# POWER.net
KiCad netlist of a schematic drawn in Altium Designer
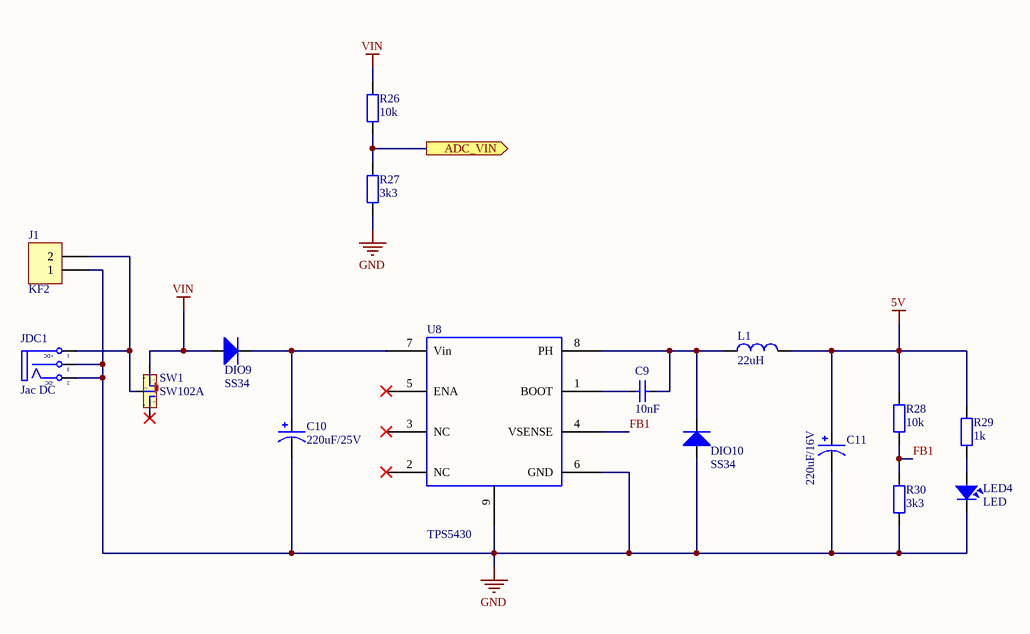
[diagram p0: POWER.SchDoc]

(export (version "E")
  (design (tool "Eeschema 10.0.6"))
  (components
    (comp (ref "C9")
      (value "10nF")
      (footprint "CAP_0805")
      (description "Capacitor")
      (fields (field (name "PUBLISHER") "Altium Limited"))
      (libsource (lib "My Library") (part "CapSMD"))
    )
    (comp (ref "C10")
      (value "220uF/25V")
      (footprint "C8mm")
      (description "Polarized Capacitor (Axial)")
      (fields (field (name "PUBLISHER") "Altium Limited"))
      (libsource (lib "My Library") (part "Cap Pol"))
    )
    (comp (ref "C11")
      (value "220uF/16V")
      (footprint "C8mm")
      (description "Polarized Capacitor (Axial)")
      (fields (field (name "PUBLISHER") "Altium Limited"))
      (libsource (lib "My Library") (part "Cap Pol"))
    )
    (comp (ref "DIO9")
      (value "SS34")
      (footprint "DIO-214AC(SMA)")
      (description "Default Diode")
      (fields (field (name "PUBLISHER") "Altium Limited"))
      (libsource (lib "My Library") (part "Diode SMD"))
    )
    (comp (ref "DIO10")
      (value "SS34")
      (footprint "DIO-214AC(SMA)")
      (description "Default Diode")
      (fields (field (name "PUBLISHER") "Altium Limited"))
      (libsource (lib "My Library") (part "Diode SMD"))
    )
    (comp (ref "J1")
      (value "KF2")
      (footprint "KF2-5.08")
      (fields
        (field (name "MANUFACTURER") "Würth Elektronik eiSos GmbH")
        (field (name "PARTNO") "691103110002")
        (field (name "CREATED BY") "Karrer Zheng")
      )
      (libsource (lib "My Library") (part "KF2"))
    )
    (comp (ref "JDC1")
      (value "Jac DC")
      (footprint "DC-IN")
      (description "Jac DC input")
      (libsource (lib "My Library") (part "DCIN"))
    )
    (comp (ref "L1")
      (value "22uH")
      (footprint "L-SMD-M-7.3x4.5")
      (description "Inductor")
      (libsource (lib "My Library") (part "Inductor"))
    )
    (comp (ref "LED4")
      (value "LED")
      (footprint "LED-0805-Red")
      (description "LED Single colour Green and Red")
      (libsource (lib "My Library") (part "LED"))
    )
    (comp (ref "R26")
      (value "10k")
      (footprint "RES-SMD-0805")
      (description "Resistor SMD")
      (fields
        (field (name "MANUFACTURER") "Generic Components")
        (field (name "PUBLISHER") "Altium Hobart Technology Centre")
      )
      (libsource (lib "My Library") (part "Resistor - SMD"))
    )
    (comp (ref "R27")
      (value "3k3")
      (footprint "RES-SMD-0805")
      (description "Resistor SMD")
      (fields
        (field (name "MANUFACTURER") "Generic Components")
        (field (name "PUBLISHER") "Altium Hobart Technology Centre")
      )
      (libsource (lib "My Library") (part "Resistor - SMD"))
    )
    (comp (ref "R28")
      (value "10k")
      (footprint "RES-SMD-0805")
      (description "Resistor SMD")
      (fields
        (field (name "MANUFACTURER") "Generic Components")
        (field (name "PUBLISHER") "Altium Hobart Technology Centre")
      )
      (libsource (lib "My Library") (part "Resistor - SMD"))
    )
    (comp (ref "R29")
      (value "1k")
      (footprint "RES-SMD-0805")
      (description "Resistor SMD")
      (fields
        (field (name "MANUFACTURER") "Generic Components")
        (field (name "PUBLISHER") "Altium Hobart Technology Centre")
      )
      (libsource (lib "My Library") (part "Resistor - SMD"))
    )
    (comp (ref "R30")
      (value "3k3")
      (footprint "RES-SMD-0805")
      (description "Resistor SMD")
      (fields
        (field (name "MANUFACTURER") "Generic Components")
        (field (name "PUBLISHER") "Altium Hobart Technology Centre")
      )
      (libsource (lib "My Library") (part "Resistor - SMD"))
    )
    (comp (ref "SW1")
      (value "SW102A")
      (footprint "SW102")
      (description "Switch 102 on Broad")
      (libsource (lib "My Library") (part "SW102A"))
    )
    (comp (ref "U8")
      (value "TPS5430")
      (footprint "ESOP-8")
      (fields (field (name "NAME") "TPS5430"))
      (libsource (lib "My Library") (part "TPS5430"))
    )
  )
  (nets
    (net (code "1") (name "/ADC_VIN") (class "Default")
      (node (ref "R26") (pin "2") (pinfunction "2_2") (pintype "passive"))
      (node (ref "R27") (pin "1") (pinfunction "1_1") (pintype "passive"))
    )
    (net (code "2") (name "/FB1") (class "Default")
      (node (ref "R28") (pin "2") (pinfunction "2_2") (pintype "passive"))
      (node (ref "R30") (pin "1") (pinfunction "1_1") (pintype "passive"))
      (node (ref "U8") (pin "4") (pinfunction "VSENSE_4") (pintype "passive"))
    )
    (net (code "3") (name "5V") (class "Default")
      (node (ref "C11") (pin "1") (pinfunction "1_1") (pintype "passive"))
      (node (ref "L1") (pin "2") (pinfunction "2_2") (pintype "passive"))
      (node (ref "R28") (pin "1") (pinfunction "1_1") (pintype "passive"))
      (node (ref "R29") (pin "1") (pinfunction "1_1") (pintype "passive"))
    )
    (net (code "4") (name "GND") (class "Default")
      (node (ref "C10") (pin "2") (pinfunction "2_2") (pintype "passive"))
      (node (ref "C11") (pin "2") (pinfunction "2_2") (pintype "passive"))
      (node (ref "DIO10") (pin "1") (pinfunction "A_1") (pintype "passive"))
      (node (ref "J1") (pin "1") (pinfunction "1_1") (pintype "passive"))
      (node (ref "JDC1") (pin "2") (pinfunction "TN_2") (pintype "passive"))
      (node (ref "JDC1") (pin "3") (pinfunction "S_3") (pintype "power_in"))
      (node (ref "LED4") (pin "2") (pinfunction "2_2") (pintype "passive"))
      (node (ref "R27") (pin "2") (pinfunction "2_2") (pintype "passive"))
      (node (ref "R30") (pin "2") (pinfunction "2_2") (pintype "passive"))
      (node (ref "U8") (pin "6") (pinfunction "GND_6") (pintype "passive"))
      (node (ref "U8") (pin "9") (pinfunction "PWR_PAD_9") (pintype "passive"))
    )
    (net (code "5") (name "Net-(DIO9-K)") (class "Default")
      (node (ref "C10") (pin "1") (pinfunction "1_1") (pintype "passive"))
      (node (ref "DIO9") (pin "2") (pinfunction "K_2") (pintype "passive"))
      (node (ref "U8") (pin "7") (pinfunction "Vin_7") (pintype "passive"))
    )
    (net (code "6") (name "Net-(DIO10-K)") (class "Default")
      (node (ref "C9") (pin "2") (pinfunction "2_2") (pintype "passive"))
      (node (ref "DIO10") (pin "2") (pinfunction "K_2") (pintype "passive"))
      (node (ref "L1") (pin "1") (pinfunction "1_1") (pintype "passive"))
      (node (ref "U8") (pin "8") (pinfunction "PH_8") (pintype "passive"))
    )
    (net (code "7") (name "Net-(JDC1-T)") (class "Default")
      (node (ref "J1") (pin "2") (pinfunction "2_2") (pintype "passive"))
      (node (ref "JDC1") (pin "1") (pinfunction "T_1") (pintype "passive"))
      (node (ref "SW1") (pin "2") (pinfunction "2_2") (pintype "passive"))
    )
    (net (code "8") (name "Net-(LED4-Pad1)") (class "Default")
      (node (ref "LED4") (pin "1") (pinfunction "1_1") (pintype "passive"))
      (node (ref "R29") (pin "2") (pinfunction "2_2") (pintype "passive"))
    )
    (net (code "9") (name "Net-(U8-BOOT)") (class "Default")
      (node (ref "C9") (pin "1") (pinfunction "1_1") (pintype "passive"))
      (node (ref "U8") (pin "1") (pinfunction "BOOT_1") (pintype "passive"))
    )
    (net (code "10") (name "VIN") (class "Default")
      (node (ref "DIO9") (pin "1") (pinfunction "A_1") (pintype "passive"))
      (node (ref "R26") (pin "1") (pinfunction "1_1") (pintype "passive"))
      (node (ref "SW1") (pin "1") (pinfunction "1_1") (pintype "passive"))
    )
    (net (code "11") (name "unconnected-(SW1-Pad3)") (class "Default")
      (node (ref "SW1") (pin "3") (pinfunction "3_3") (pintype "passive+no_connect"))
    )
    (net (code "12") (name "unconnected-(SW1-Pad4)") (class "Default")
      (node (ref "SW1") (pin "4") (pinfunction "4_4") (pintype "passive"))
    )
    (net (code "13") (name "unconnected-(SW1-Pad5)") (class "Default")
      (node (ref "SW1") (pin "5") (pinfunction "5_5") (pintype "passive"))
    )
    (net (code "14") (name "unconnected-(U8-ENA-Pad5)") (class "Default")
      (node (ref "U8") (pin "5") (pinfunction "ENA_5") (pintype "passive+no_connect"))
    )
    (net (code "15") (name "unconnected-(U8-NC-Pad2)") (class "Default")
      (node (ref "U8") (pin "2") (pinfunction "NC_2") (pintype "passive+no_connect"))
    )
    (net (code "16") (name "unconnected-(U8-NC-Pad3)") (class "Default")
      (node (ref "U8") (pin "3") (pinfunction "NC_3") (pintype "passive+no_connect"))
    )
  )
)
